# RHS.net
KiCad netlist of a schematic drawn in Altium Designer
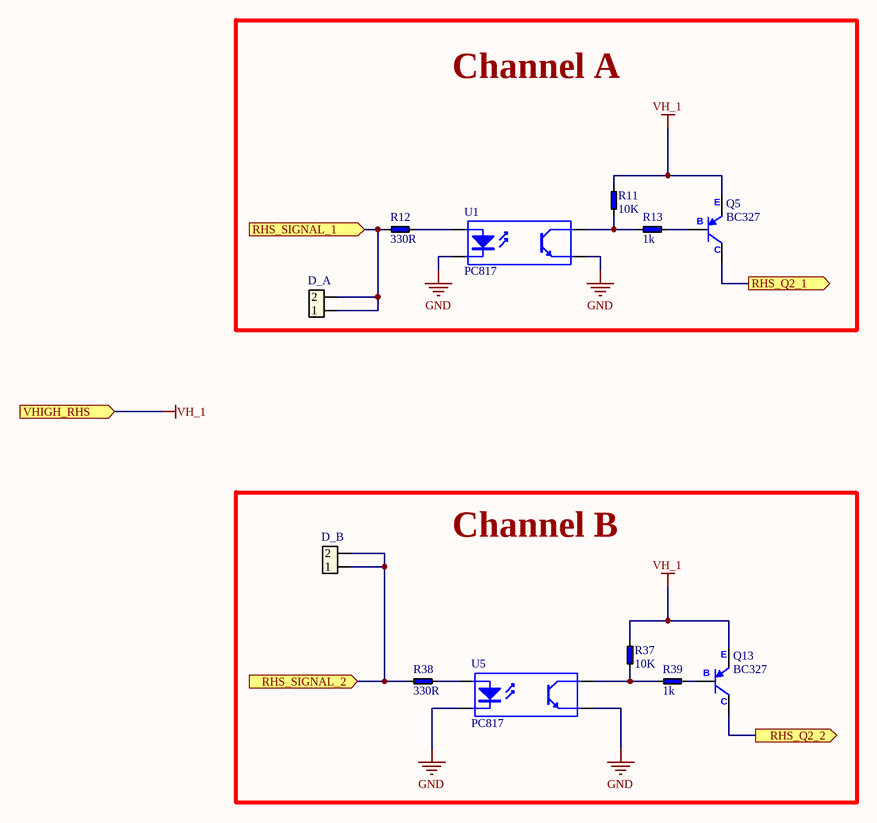
[diagram p0: RHS.SchDoc]

(export (version "E")
  (design (tool "Eeschema 10.0.6"))
  (components
    (comp (ref "D_A")
      (value "Header 2")
      (footprint "PINHEADER X2")
      (description "Header, 2-Pin")
      (fields (field (name "PUBLISHER") "Altium Limited"))
      (libsource (lib "Altium_Abbas") (part "Header 2"))
    )
    (comp (ref "D_B")
      (value "Header 2")
      (footprint "PINHEADER X2")
      (description "Header, 2-Pin")
      (fields (field (name "PUBLISHER") "Altium Limited"))
      (libsource (lib "Altium_Abbas") (part "Header 2"))
    )
    (comp (ref "Q5")
      (value "BC327")
      (footprint "Transistor - duplicate3")
      (libsource (lib "Altium_Abbas") (part "PNP"))
    )
    (comp (ref "Q13")
      (value "BC327")
      (footprint "Transistor - duplicate3")
      (libsource (lib "Altium_Abbas") (part "PNP"))
    )
    (comp (ref "R11")
      (value "10K")
      (footprint "RESISTOR _9")
      (libsource (lib "Altium_Abbas") (part "RESISTOR"))
    )
    (comp (ref "R12")
      (value "330R")
      (footprint "RESISTOR _9")
      (libsource (lib "Altium_Abbas") (part "RESISTOR"))
    )
    (comp (ref "R13")
      (value "1k")
      (footprint "RESISTOR _9")
      (libsource (lib "Altium_Abbas") (part "RESISTOR"))
    )
    (comp (ref "R37")
      (value "10K")
      (footprint "RESISTOR _9")
      (libsource (lib "Altium_Abbas") (part "RESISTOR"))
    )
    (comp (ref "R38")
      (value "330R")
      (footprint "RESISTOR _9")
      (libsource (lib "Altium_Abbas") (part "RESISTOR"))
    )
    (comp (ref "R39")
      (value "1k")
      (footprint "RESISTOR _9")
      (libsource (lib "Altium_Abbas") (part "RESISTOR"))
    )
    (comp (ref "U1")
      (value "PC817")
      (footprint "IC X4 PIN")
      (description "4-Pin Phototransistor Optocoupler")
      (fields (field (name "PUBLISHER") "Altium Limited"))
      (libsource (lib "Altium_Abbas") (part "Opto-coupler"))
    )
    (comp (ref "U5")
      (value "PC817")
      (footprint "IC X4 PIN")
      (description "4-Pin Phototransistor Optocoupler")
      (fields (field (name "PUBLISHER") "Altium Limited"))
      (libsource (lib "Altium_Abbas") (part "Opto-coupler"))
    )
  )
  (nets
    (net (code "1") (name "/RHS_Q2_1") (class "Default")
      (node (ref "Q5") (pin "3") (pinfunction "C_3") (pintype "passive"))
    )
    (net (code "2") (name "/RHS_Q2_2") (class "Default")
      (node (ref "Q13") (pin "3") (pinfunction "C_3") (pintype "passive"))
    )
    (net (code "3") (name "/RHS_SIGNAL_1") (class "Default")
      (node (ref "D_A") (pin "1") (pinfunction "1_1") (pintype "passive"))
      (node (ref "D_A") (pin "2") (pinfunction "2_2") (pintype "passive"))
      (node (ref "R12") (pin "1") (pinfunction "5_1") (pintype "passive"))
    )
    (net (code "4") (name "/RHS_SIGNAL_2") (class "Default")
      (node (ref "D_B") (pin "1") (pinfunction "1_1") (pintype "passive"))
      (node (ref "D_B") (pin "2") (pinfunction "2_2") (pintype "passive"))
      (node (ref "R38") (pin "1") (pinfunction "5_1") (pintype "passive"))
    )
    (net (code "5") (name "GND") (class "Default")
      (node (ref "U1") (pin "2") (pinfunction "K_2") (pintype "passive"))
      (node (ref "U1") (pin "3") (pinfunction "E_3") (pintype "passive"))
      (node (ref "U5") (pin "2") (pinfunction "K_2") (pintype "passive"))
      (node (ref "U5") (pin "3") (pinfunction "E_3") (pintype "passive"))
    )
    (net (code "6") (name "Net-(Q5-B)") (class "Default")
      (node (ref "Q5") (pin "2") (pinfunction "B_2") (pintype "passive"))
      (node (ref "R13") (pin "2") (pinfunction "6_2") (pintype "passive"))
    )
    (net (code "7") (name "Net-(Q13-B)") (class "Default")
      (node (ref "Q13") (pin "2") (pinfunction "B_2") (pintype "passive"))
      (node (ref "R39") (pin "2") (pinfunction "6_2") (pintype "passive"))
    )
    (net (code "8") (name "Net-(R11-5)") (class "Default")
      (node (ref "R11") (pin "1") (pinfunction "5_1") (pintype "passive"))
      (node (ref "R13") (pin "1") (pinfunction "5_1") (pintype "passive"))
      (node (ref "U1") (pin "4") (pinfunction "C_4") (pintype "passive"))
    )
    (net (code "9") (name "Net-(R12-6)") (class "Default")
      (node (ref "R12") (pin "2") (pinfunction "6_2") (pintype "passive"))
      (node (ref "U1") (pin "1") (pinfunction "A_1") (pintype "passive"))
    )
    (net (code "10") (name "Net-(R37-5)") (class "Default")
      (node (ref "R37") (pin "1") (pinfunction "5_1") (pintype "passive"))
      (node (ref "R39") (pin "1") (pinfunction "5_1") (pintype "passive"))
      (node (ref "U5") (pin "4") (pinfunction "C_4") (pintype "passive"))
    )
    (net (code "11") (name "Net-(R38-6)") (class "Default")
      (node (ref "R38") (pin "2") (pinfunction "6_2") (pintype "passive"))
      (node (ref "U5") (pin "1") (pinfunction "A_1") (pintype "passive"))
    )
    (net (code "12") (name "VH_1") (class "Default")
      (node (ref "Q13") (pin "1") (pinfunction "E_1") (pintype "passive"))
      (node (ref "Q5") (pin "1") (pinfunction "E_1") (pintype "passive"))
      (node (ref "R11") (pin "2") (pinfunction "6_2") (pintype "passive"))
      (node (ref "R37") (pin "2") (pinfunction "6_2") (pintype "passive"))
    )
  )
)
